# QuadDacDriver.net
KiCad netlist of a schematic drawn in Altium Designer
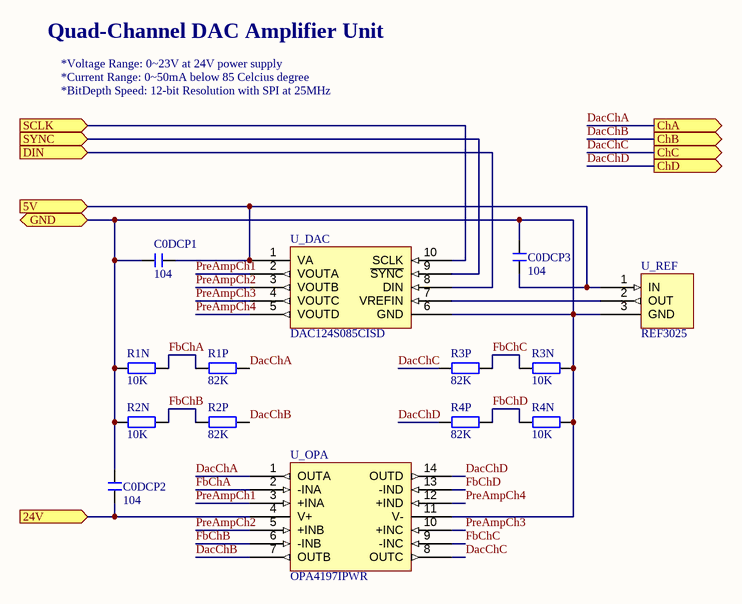
[diagram p0: QuadDacDriver.SchDoc]

(export (version "E")
  (design (tool "Eeschema 10.0.6"))
  (components
    (comp (ref "C0DCP1")
      (value "104")
      (footprint "C 0603_L")
      (description "贴片电容")
      (libsource (lib "0.1 - 电阻-电容-电感") (part "C"))
    )
    (comp (ref "C0DCP2")
      (value "104")
      (footprint "C 0603_L")
      (description "贴片电容")
      (libsource (lib "0.1 - 电阻-电容-电感") (part "C"))
    )
    (comp (ref "C0DCP3")
      (value "104")
      (footprint "C 0603_L")
      (description "贴片电容")
      (libsource (lib "0.1 - 电阻-电容-电感") (part "C"))
    )
    (comp (ref "R1N")
      (value "10K")
      (footprint "R 0603_L")
      (description "贴片电阻")
      (fields (field (name "版权归属") "来自淘宝 ID：黄晶宝石"))
      (libsource (lib "0.1 - 电阻-电容-电感") (part "R"))
    )
    (comp (ref "R1P")
      (value "82K")
      (footprint "R 0603_L")
      (description "贴片电阻")
      (fields (field (name "版权归属") "来自淘宝 ID：黄晶宝石"))
      (libsource (lib "0.1 - 电阻-电容-电感") (part "R"))
    )
    (comp (ref "R2N")
      (value "10K")
      (footprint "R 0603_L")
      (description "贴片电阻")
      (fields (field (name "版权归属") "来自淘宝 ID：黄晶宝石"))
      (libsource (lib "0.1 - 电阻-电容-电感") (part "R"))
    )
    (comp (ref "R2P")
      (value "82K")
      (footprint "R 0603_L")
      (description "贴片电阻")
      (fields (field (name "版权归属") "来自淘宝 ID：黄晶宝石"))
      (libsource (lib "0.1 - 电阻-电容-电感") (part "R"))
    )
    (comp (ref "R3N")
      (value "10K")
      (footprint "R 0603_L")
      (description "贴片电阻")
      (fields (field (name "版权归属") "来自淘宝 ID：黄晶宝石"))
      (libsource (lib "0.1 - 电阻-电容-电感") (part "R"))
    )
    (comp (ref "R3P")
      (value "82K")
      (footprint "R 0603_L")
      (description "贴片电阻")
      (fields (field (name "版权归属") "来自淘宝 ID：黄晶宝石"))
      (libsource (lib "0.1 - 电阻-电容-电感") (part "R"))
    )
    (comp (ref "R4N")
      (value "10K")
      (footprint "R 0603_L")
      (description "贴片电阻")
      (fields (field (name "版权归属") "来自淘宝 ID：黄晶宝石"))
      (libsource (lib "0.1 - 电阻-电容-电感") (part "R"))
    )
    (comp (ref "R4P")
      (value "82K")
      (footprint "R 0603_L")
      (description "贴片电阻")
      (fields (field (name "版权归属") "来自淘宝 ID：黄晶宝石"))
      (libsource (lib "0.1 - 电阻-电容-电感") (part "R"))
    )
    (comp (ref "U_DAC")
      (value "DAC124S085CISD")
      (footprint "VSSOP-10")
      (description "TI 10-bit Quad-channel DAC (NOPB)")
      (libsource (lib "CustomizedComponents") (part "DAC104S085CISD"))
    )
    (comp (ref "U_OPA")
      (value "OPA4197IPWR")
      (footprint "TSSOP-14")
      (description "Quad-channel Operational Amplifier")
      (libsource (lib "CustomizedComponents") (part "OPA4197IPWR"))
    )
    (comp (ref "U_REF")
      (value "REF3025")
      (footprint "SOT23-3")
      (description "3V Reference Source")
      (libsource (lib "CustomizedComponents") (part "REF3030AIDBZT"))
    )
  )
  (nets
    (net (code "1") (name "/5V") (class "Default")
      (node (ref "C0DCP1") (pin "1") (pinfunction "1_1") (pintype "passive"))
      (node (ref "C0DCP3") (pin "2") (pinfunction "2_2") (pintype "passive"))
      (node (ref "U_DAC") (pin "1") (pinfunction "VA_1") (pintype "passive"))
      (node (ref "U_REF") (pin "1") (pinfunction "IN_1") (pintype "input"))
    )
    (net (code "2") (name "/24V") (class "Default")
      (node (ref "C0DCP2") (pin "1") (pinfunction "1_1") (pintype "passive"))
      (node (ref "U_OPA") (pin "4") (pinfunction "V+_4") (pintype "passive"))
    )
    (net (code "3") (name "/DIN") (class "Default")
      (node (ref "U_DAC") (pin "8") (pinfunction "DIN_8") (pintype "input"))
    )
    (net (code "4") (name "/DacChA") (class "Default")
      (node (ref "R1P") (pin "2") (pinfunction "2_2") (pintype "passive"))
      (node (ref "U_OPA") (pin "1") (pinfunction "OUTA_1") (pintype "output"))
    )
    (net (code "5") (name "/DacChB") (class "Default")
      (node (ref "R2P") (pin "2") (pinfunction "2_2") (pintype "passive"))
      (node (ref "U_OPA") (pin "7") (pinfunction "OUTB_7") (pintype "output"))
    )
    (net (code "6") (name "/DacChC") (class "Default")
      (node (ref "R3P") (pin "1") (pinfunction "1_1") (pintype "passive"))
      (node (ref "U_OPA") (pin "8") (pinfunction "OUTC_8") (pintype "output"))
    )
    (net (code "7") (name "/DacChD") (class "Default")
      (node (ref "R4P") (pin "1") (pinfunction "1_1") (pintype "passive"))
      (node (ref "U_OPA") (pin "14") (pinfunction "OUTD_14") (pintype "output"))
    )
    (net (code "8") (name "/FbChA") (class "Default")
      (node (ref "R1N") (pin "2") (pinfunction "2_2") (pintype "passive"))
      (node (ref "R1P") (pin "1") (pinfunction "1_1") (pintype "passive"))
      (node (ref "U_OPA") (pin "2") (pinfunction "-INA_2") (pintype "input"))
    )
    (net (code "9") (name "/FbChB") (class "Default")
      (node (ref "R2N") (pin "2") (pinfunction "2_2") (pintype "passive"))
      (node (ref "R2P") (pin "1") (pinfunction "1_1") (pintype "passive"))
      (node (ref "U_OPA") (pin "6") (pinfunction "-INB_6") (pintype "input"))
    )
    (net (code "10") (name "/FbChC") (class "Default")
      (node (ref "R3N") (pin "1") (pinfunction "1_1") (pintype "passive"))
      (node (ref "R3P") (pin "2") (pinfunction "2_2") (pintype "passive"))
      (node (ref "U_OPA") (pin "9") (pinfunction "-INC_9") (pintype "input"))
    )
    (net (code "11") (name "/FbChD") (class "Default")
      (node (ref "R4N") (pin "1") (pinfunction "1_1") (pintype "passive"))
      (node (ref "R4P") (pin "2") (pinfunction "2_2") (pintype "passive"))
      (node (ref "U_OPA") (pin "13") (pinfunction "-IND_13") (pintype "input"))
    )
    (net (code "12") (name "/GND") (class "Default")
      (node (ref "C0DCP1") (pin "2") (pinfunction "2_2") (pintype "passive"))
      (node (ref "C0DCP2") (pin "2") (pinfunction "2_2") (pintype "passive"))
      (node (ref "C0DCP3") (pin "1") (pinfunction "1_1") (pintype "passive"))
      (node (ref "R1N") (pin "1") (pinfunction "1_1") (pintype "passive"))
      (node (ref "R2N") (pin "1") (pinfunction "1_1") (pintype "passive"))
      (node (ref "R3N") (pin "2") (pinfunction "2_2") (pintype "passive"))
      (node (ref "R4N") (pin "2") (pinfunction "2_2") (pintype "passive"))
      (node (ref "U_DAC") (pin "6") (pinfunction "GND_6") (pintype "passive"))
      (node (ref "U_OPA") (pin "11") (pinfunction "V-_11") (pintype "passive"))
      (node (ref "U_REF") (pin "3") (pinfunction "GND_3") (pintype "passive"))
    )
    (net (code "13") (name "/PreAmpCh1") (class "Default")
      (node (ref "U_DAC") (pin "2") (pinfunction "VOUTA_2") (pintype "output"))
      (node (ref "U_OPA") (pin "3") (pinfunction "+INA_3") (pintype "input"))
    )
    (net (code "14") (name "/PreAmpCh2") (class "Default")
      (node (ref "U_DAC") (pin "3") (pinfunction "VOUTB_3") (pintype "output"))
      (node (ref "U_OPA") (pin "5") (pinfunction "+INB_5") (pintype "input"))
    )
    (net (code "15") (name "/PreAmpCh3") (class "Default")
      (node (ref "U_DAC") (pin "4") (pinfunction "VOUTC_4") (pintype "output"))
      (node (ref "U_OPA") (pin "10") (pinfunction "+INC_10") (pintype "input"))
    )
    (net (code "16") (name "/PreAmpCh4") (class "Default")
      (node (ref "U_DAC") (pin "5") (pinfunction "VOUTD_5") (pintype "output"))
      (node (ref "U_OPA") (pin "12") (pinfunction "+IND_12") (pintype "input"))
    )
    (net (code "17") (name "/SCLK") (class "Default")
      (node (ref "U_DAC") (pin "10") (pinfunction "SCLK_10") (pintype "input"))
    )
    (net (code "18") (name "/SYNC") (class "Default")
      (node (ref "U_DAC") (pin "9") (pinfunction "SYNC_9") (pintype "input"))
    )
    (net (code "19") (name "Net-(U_DAC-VREFIN)") (class "Default")
      (node (ref "U_DAC") (pin "7") (pinfunction "VREFIN_7") (pintype "input"))
      (node (ref "U_REF") (pin "2") (pinfunction "OUT_2") (pintype "output"))
    )
  )
)
